# DM3390_BOOT_JTAG_SD.net
KiCad netlist of a schematic drawn in Altium Designer
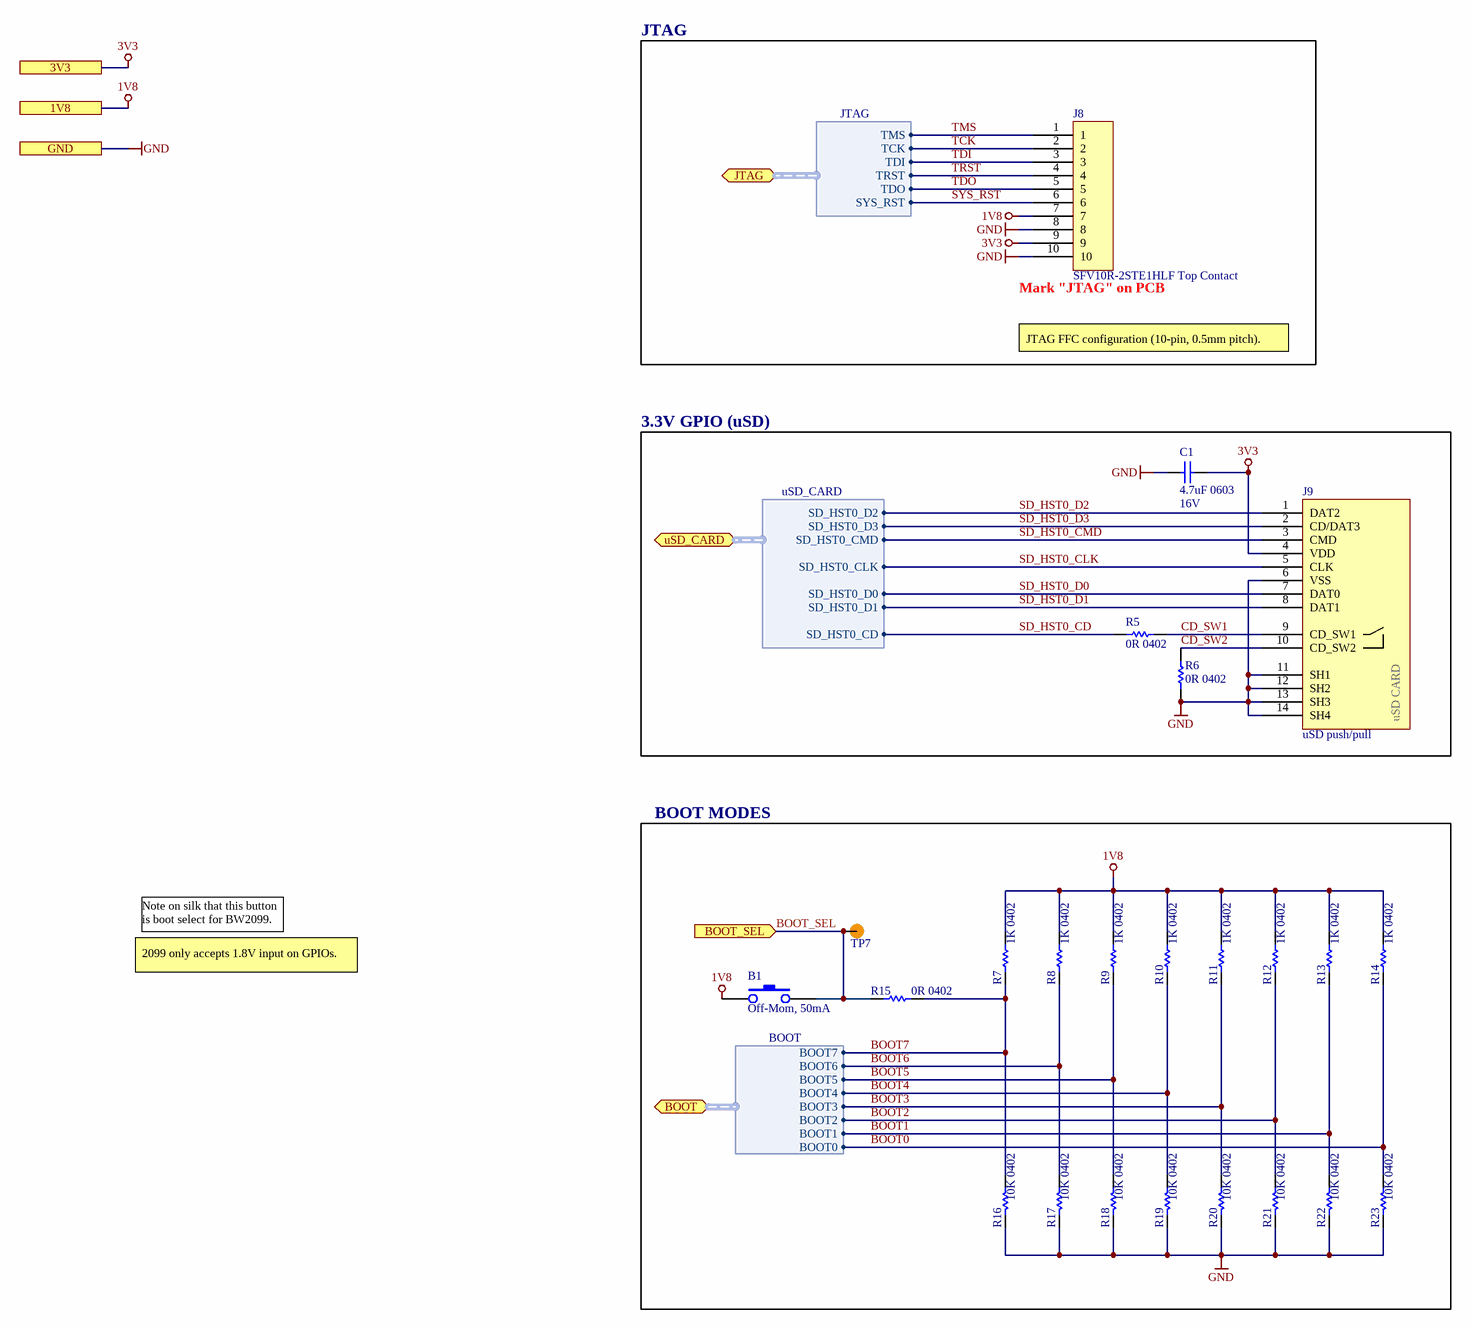
[diagram p0: DM3390_BOOT_JTAG_SD.SchDoc]

(export (version "E")
  (design (tool "Eeschema 10.0.6"))
  (components
    (comp (ref "B1")
      (value "Off-Mom, 50mA")
      (footprint "LuxonisMaster:DTSM-32N-V")
      (description "SWITCH TACTILE SMT 3.5mm * 6mm , brown 160gf")
      (libsource (lib "LuxonisMaster") (part "DTSM-32N-V"))
    )
    (comp (ref "C1")
      (value "4.7uF 0603")
      (footprint "CAPC0603(1608)100_N")
      (description "CAP CER 4.7UF 16V X5R 0603 10%")
      (fields (field (name "TOLERANCE") "10%") (field (name "VOLTAGE RATING") "16V"))
      (libsource (lib "LuxonisMaster") (part "GRM188R61C475KAAJD"))
    )
    (comp (ref "J8")
      (value "SFV10R-2STE1HLF Top Contact")
      (footprint "LuxonisMaster:SFV10R-2STE1HLF")
      (description "CONN FFC TOP 10POS 0.50MM R/A")
      (libsource (lib "LuxonisMaster") (part "SFV10R-2STE1HLF"))
    )
    (comp (ref "J9")
      (value "uSD push/pull")
      (footprint "LuxonisMaster:104031-0811")
      (description "CONN MICRO SD CARD PUSH-PULL R/A")
      (libsource (lib "LuxonisMaster") (part "104031-0811"))
    )
    (comp (ref "R5")
      (value "0R 0402")
      (footprint "RESC0402(1005)_N")
      (description "RES SMD 0 OHM JUMPER 1/16W 0402")
      (fields (field (name "TOLERANCE") "5%"))
      (libsource (lib "LuxonisMaster") (part "CRCW04020000Z0ED"))
    )
    (comp (ref "R6")
      (value "0R 0402")
      (footprint "RESC0402(1005)_N")
      (description "RES SMD 0 OHM JUMPER 1/16W 0402")
      (fields (field (name "TOLERANCE") "5%"))
      (libsource (lib "LuxonisMaster") (part "CRCW04020000Z0ED"))
    )
    (comp (ref "R7")
      (value "1K 0402")
      (footprint "RES_Altium_Vault_Generic:RESC0402(1005)_L")
      (fields (field (name "TOLERANCE") "1%"))
      (libsource (lib "LuxonisMaster") (part "RC0402FR-071KL"))
    )
    (comp (ref "R8")
      (value "1K 0402")
      (footprint "RES_Altium_Vault_Generic:RESC0402(1005)_L")
      (fields (field (name "TOLERANCE") "1%"))
      (libsource (lib "LuxonisMaster") (part "RC0402FR-071KL"))
    )
    (comp (ref "R9")
      (value "1K 0402")
      (footprint "RES_Altium_Vault_Generic:RESC0402(1005)_L")
      (fields (field (name "TOLERANCE") "1%"))
      (libsource (lib "LuxonisMaster") (part "RC0402FR-071KL"))
    )
    (comp (ref "R10")
      (value "1K 0402")
      (footprint "RES_Altium_Vault_Generic:RESC0402(1005)_L")
      (fields (field (name "TOLERANCE") "1%"))
      (libsource (lib "LuxonisMaster") (part "RC0402FR-071KL"))
    )
    (comp (ref "R11")
      (value "1K 0402")
      (footprint "RES_Altium_Vault_Generic:RESC0402(1005)_L")
      (fields (field (name "TOLERANCE") "1%"))
      (libsource (lib "LuxonisMaster") (part "RC0402FR-071KL"))
    )
    (comp (ref "R12")
      (value "1K 0402")
      (footprint "RES_Altium_Vault_Generic:RESC0402(1005)_L")
      (fields (field (name "TOLERANCE") "1%"))
      (libsource (lib "LuxonisMaster") (part "RC0402FR-071KL"))
    )
    (comp (ref "R13")
      (value "1K 0402")
      (footprint "RES_Altium_Vault_Generic:RESC0402(1005)_L")
      (fields (field (name "TOLERANCE") "1%"))
      (libsource (lib "LuxonisMaster") (part "RC0402FR-071KL"))
    )
    (comp (ref "R14")
      (value "1K 0402")
      (footprint "RES_Altium_Vault_Generic:RESC0402(1005)_L")
      (fields (field (name "TOLERANCE") "1%"))
      (libsource (lib "LuxonisMaster") (part "RC0402FR-071KL"))
    )
    (comp (ref "R15")
      (value "0R 0402")
      (footprint "RES_Altium_Vault_Generic:RESC0402(1005)_L")
      (description "RES SMD 0 OHM JUMPER 1/16W 0402")
      (fields (field (name "TOLERANCE") "5%"))
      (libsource (lib "LuxonisMaster") (part "CRCW04020000Z0ED"))
    )
    (comp (ref "R16")
      (value "10K 0402")
      (footprint "RES_Altium_Vault_Generic:RESC0402(1005)_L")
      (fields (field (name "TOLERANCE") "1%"))
      (libsource (lib "LuxonisMaster") (part "RC0402FR-1310KL"))
    )
    (comp (ref "R17")
      (value "10K 0402")
      (footprint "RES_Altium_Vault_Generic:RESC0402(1005)_L")
      (fields (field (name "TOLERANCE") "1%"))
      (libsource (lib "LuxonisMaster") (part "RC0402FR-1310KL"))
    )
    (comp (ref "R18")
      (value "10K 0402")
      (footprint "RES_Altium_Vault_Generic:RESC0402(1005)_L")
      (fields (field (name "TOLERANCE") "1%"))
      (libsource (lib "LuxonisMaster") (part "RC0402FR-1310KL"))
    )
    (comp (ref "R19")
      (value "10K 0402")
      (footprint "RES_Altium_Vault_Generic:RESC0402(1005)_L")
      (fields (field (name "TOLERANCE") "1%"))
      (libsource (lib "LuxonisMaster") (part "RC0402FR-1310KL"))
    )
    (comp (ref "R20")
      (value "10K 0402")
      (footprint "RES_Altium_Vault_Generic:RESC0402(1005)_L")
      (fields (field (name "TOLERANCE") "1%"))
      (libsource (lib "LuxonisMaster") (part "RC0402FR-1310KL"))
    )
    (comp (ref "R21")
      (value "10K 0402")
      (footprint "RES_Altium_Vault_Generic:RESC0402(1005)_L")
      (fields (field (name "TOLERANCE") "1%"))
      (libsource (lib "LuxonisMaster") (part "RC0402FR-1310KL"))
    )
    (comp (ref "R22")
      (value "10K 0402")
      (footprint "RES_Altium_Vault_Generic:RESC0402(1005)_L")
      (fields (field (name "TOLERANCE") "1%"))
      (libsource (lib "LuxonisMaster") (part "RC0402FR-1310KL"))
    )
    (comp (ref "R23")
      (value "10K 0402")
      (footprint "RES_Altium_Vault_Generic:RESC0402(1005)_L")
      (fields (field (name "TOLERANCE") "1%"))
      (libsource (lib "LuxonisMaster") (part "RC0402FR-1310KL"))
    )
    (comp (ref "TP7")
      (value "TP100_200_NS")
      (footprint "LuxonisMaster:TP100_200_NS")
      (libsource (lib "LuxonisMaster") (part "TEST_POINT"))
    )
  )
  (nets
    (net (code "4") (name "/BOOT0") (class "Default")
      (node (ref "R14") (pin "1") (pinfunction "1_1") (pintype "passive"))
      (node (ref "R23") (pin "1") (pinfunction "1_1") (pintype "passive"))
    )
    (net (code "5") (name "/BOOT1") (class "Default")
      (node (ref "R13") (pin "1") (pinfunction "1_1") (pintype "passive"))
      (node (ref "R22") (pin "1") (pinfunction "1_1") (pintype "passive"))
    )
    (net (code "6") (name "/BOOT2") (class "Default")
      (node (ref "R12") (pin "1") (pinfunction "1_1") (pintype "passive"))
      (node (ref "R21") (pin "1") (pinfunction "1_1") (pintype "passive"))
    )
    (net (code "7") (name "/BOOT3") (class "Default")
      (node (ref "R11") (pin "1") (pinfunction "1_1") (pintype "passive"))
      (node (ref "R20") (pin "1") (pinfunction "1_1") (pintype "passive"))
    )
    (net (code "8") (name "/BOOT4") (class "Default")
      (node (ref "R10") (pin "1") (pinfunction "1_1") (pintype "passive"))
      (node (ref "R19") (pin "1") (pinfunction "1_1") (pintype "passive"))
    )
    (net (code "9") (name "/BOOT5") (class "Default")
      (node (ref "R18") (pin "1") (pinfunction "1_1") (pintype "passive"))
      (node (ref "R9") (pin "1") (pinfunction "1_1") (pintype "passive"))
    )
    (net (code "10") (name "/BOOT6") (class "Default")
      (node (ref "R17") (pin "1") (pinfunction "1_1") (pintype "passive"))
      (node (ref "R8") (pin "1") (pinfunction "1_1") (pintype "passive"))
    )
    (net (code "11") (name "/BOOT7") (class "Default")
      (node (ref "R15") (pin "1") (pinfunction "1_1") (pintype "passive"))
      (node (ref "R16") (pin "1") (pinfunction "1_1") (pintype "passive"))
      (node (ref "R7") (pin "1") (pinfunction "1_1") (pintype "passive"))
    )
    (net (code "12") (name "/BOOT_SEL") (class "Default")
      (node (ref "B1") (pin "2") (pinfunction "2_2") (pintype "passive"))
      (node (ref "R15") (pin "2") (pinfunction "2_2") (pintype "passive"))
      (node (ref "TP7") (pin "1") (pintype "passive"))
    )
    (net (code "13") (name "/CD_SW1") (class "Default")
      (node (ref "J9") (pin "9") (pinfunction "CD_SW1_9") (pintype "passive"))
      (node (ref "R5") (pin "1") (pinfunction "1_1") (pintype "passive"))
    )
    (net (code "14") (name "/CD_SW2") (class "Default")
      (node (ref "J9") (pin "10") (pinfunction "CD_SW2_10") (pintype "passive"))
      (node (ref "R6") (pin "2") (pinfunction "2_2") (pintype "passive"))
    )
    (net (code "15") (name "/SD_HST0_CD") (class "Default")
      (node (ref "R5") (pin "2") (pinfunction "2_2") (pintype "passive"))
    )
    (net (code "16") (name "/SD_HST0_CLK") (class "Default")
      (node (ref "J9") (pin "5") (pinfunction "CLK_5") (pintype "passive"))
    )
    (net (code "17") (name "/SD_HST0_CMD") (class "Default")
      (node (ref "J9") (pin "3") (pinfunction "CMD_3") (pintype "passive"))
    )
    (net (code "18") (name "/SD_HST0_D0") (class "Default")
      (node (ref "J9") (pin "7") (pinfunction "DAT0_7") (pintype "passive"))
    )
    (net (code "19") (name "/SD_HST0_D1") (class "Default")
      (node (ref "J9") (pin "8") (pinfunction "DAT1_8") (pintype "passive"))
    )
    (net (code "20") (name "/SD_HST0_D2") (class "Default")
      (node (ref "J9") (pin "1") (pinfunction "DAT2_1") (pintype "passive"))
    )
    (net (code "21") (name "/SD_HST0_D3") (class "Default")
      (node (ref "J9") (pin "2") (pinfunction "CD/DAT3_2") (pintype "passive"))
    )
    (net (code "22") (name "/SYS_RST") (class "Default")
      (node (ref "J8") (pin "6") (pinfunction "6_6") (pintype "passive"))
    )
    (net (code "23") (name "/TCK") (class "Default")
      (node (ref "J8") (pin "2") (pinfunction "2_2") (pintype "passive"))
    )
    (net (code "24") (name "/TDI") (class "Default")
      (node (ref "J8") (pin "3") (pinfunction "3_3") (pintype "passive"))
    )
    (net (code "25") (name "/TDO") (class "Default")
      (node (ref "J8") (pin "5") (pinfunction "5_5") (pintype "passive"))
    )
    (net (code "26") (name "/TMS") (class "Default")
      (node (ref "J8") (pin "1") (pinfunction "1_1") (pintype "passive"))
    )
    (net (code "27") (name "/TRST") (class "Default")
      (node (ref "J8") (pin "4") (pinfunction "4_4") (pintype "passive"))
    )
    (net (code "31") (name "1V8") (class "Default")
      (node (ref "B1") (pin "1") (pinfunction "1_1") (pintype "passive"))
      (node (ref "J8") (pin "7") (pinfunction "7_7") (pintype "passive"))
      (node (ref "R10") (pin "2") (pinfunction "2_2") (pintype "passive"))
      (node (ref "R11") (pin "2") (pinfunction "2_2") (pintype "passive"))
      (node (ref "R12") (pin "2") (pinfunction "2_2") (pintype "passive"))
      (node (ref "R13") (pin "2") (pinfunction "2_2") (pintype "passive"))
      (node (ref "R14") (pin "2") (pinfunction "2_2") (pintype "passive"))
      (node (ref "R7") (pin "2") (pinfunction "2_2") (pintype "passive"))
      (node (ref "R8") (pin "2") (pinfunction "2_2") (pintype "passive"))
      (node (ref "R9") (pin "2") (pinfunction "2_2") (pintype "passive"))
    )
    (net (code "32") (name "3V3") (class "Default")
      (node (ref "C1") (pin "2") (pinfunction "2_2") (pintype "passive"))
      (node (ref "J8") (pin "9") (pinfunction "9_9") (pintype "passive"))
      (node (ref "J9") (pin "4") (pinfunction "VDD_4") (pintype "passive"))
    )
    (net (code "33") (name "GND") (class "Default")
      (node (ref "C1") (pin "1") (pinfunction "1_1") (pintype "passive"))
      (node (ref "J8") (pin "10") (pinfunction "10_10") (pintype "passive"))
      (node (ref "J8") (pin "8") (pinfunction "8_8") (pintype "passive"))
      (node (ref "J9") (pin "11") (pinfunction "SH1_11") (pintype "passive"))
      (node (ref "J9") (pin "12") (pinfunction "SH2_12") (pintype "passive"))
      (node (ref "J9") (pin "13") (pinfunction "SH3_13") (pintype "passive"))
      (node (ref "J9") (pin "14") (pinfunction "SH4_14") (pintype "passive"))
      (node (ref "J9") (pin "6") (pinfunction "VSS_6") (pintype "passive"))
      (node (ref "R16") (pin "2") (pinfunction "2_2") (pintype "passive"))
      (node (ref "R17") (pin "2") (pinfunction "2_2") (pintype "passive"))
      (node (ref "R18") (pin "2") (pinfunction "2_2") (pintype "passive"))
      (node (ref "R19") (pin "2") (pinfunction "2_2") (pintype "passive"))
      (node (ref "R20") (pin "2") (pinfunction "2_2") (pintype "passive"))
      (node (ref "R21") (pin "2") (pinfunction "2_2") (pintype "passive"))
      (node (ref "R22") (pin "2") (pinfunction "2_2") (pintype "passive"))
      (node (ref "R23") (pin "2") (pinfunction "2_2") (pintype "passive"))
      (node (ref "R6") (pin "1") (pinfunction "1_1") (pintype "passive"))
    )
  )
)
